# UART-Interface.net
KiCad netlist of a schematic drawn in Altium Designer
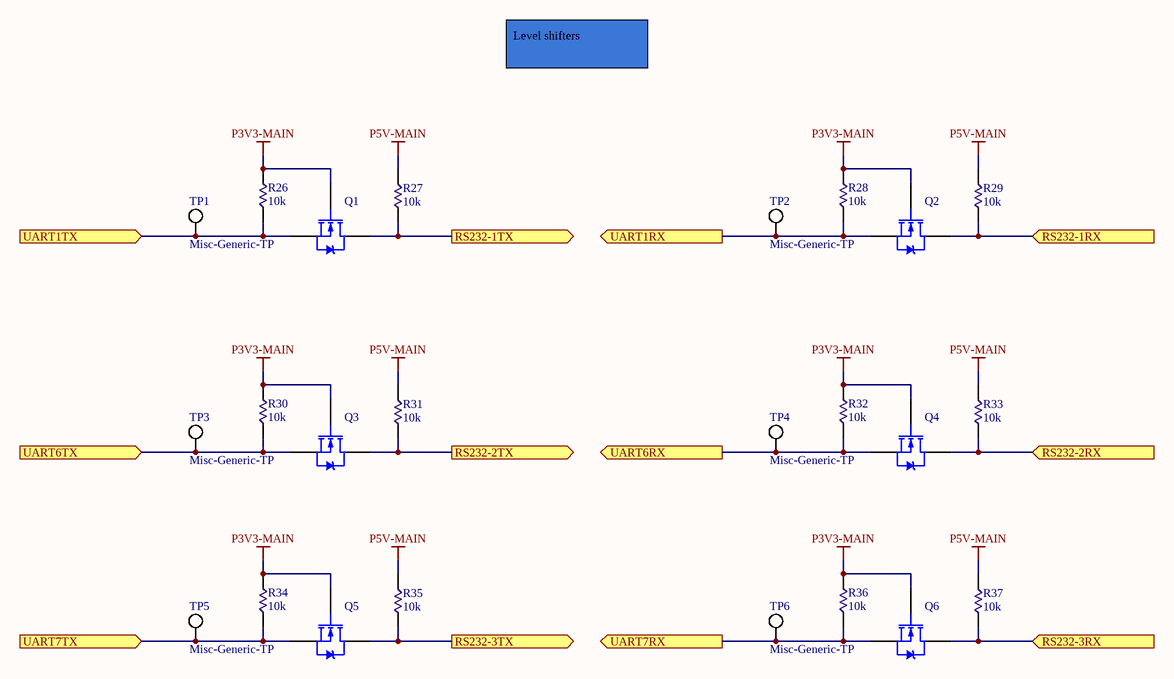
[diagram p0: UART-Interface.SchDoc]

(export (version "E")
  (design (tool "Eeschema 10.0.6"))
  (components
    (comp (ref "Q1")
      (value "BSS138Q-7-F")
      (footprint "FOOTPRINT-DINC-SOT23-1G2S3D")
      (description "N-Channel Logic Level Enhancement Mode Field Effect Transistor")
      (fields (field (name "PUBLISHER") "Altium Limited"))
      (libsource (lib "HR-Master-Integrated") (part "Transistor-DiodesInc-BSS138-1G2S3D"))
    )
    (comp (ref "Q2")
      (value "BSS138Q-7-F")
      (footprint "FOOTPRINT-DINC-SOT23-1G2S3D")
      (description "N-Channel Logic Level Enhancement Mode Field Effect Transistor")
      (fields (field (name "PUBLISHER") "Altium Limited"))
      (libsource (lib "HR-Master-Integrated") (part "Transistor-DiodesInc-BSS138-1G2S3D"))
    )
    (comp (ref "Q3")
      (value "BSS138Q-7-F")
      (footprint "FOOTPRINT-DINC-SOT23-1G2S3D")
      (description "N-Channel Logic Level Enhancement Mode Field Effect Transistor")
      (fields (field (name "PUBLISHER") "Altium Limited"))
      (libsource (lib "HR-Master-Integrated") (part "Transistor-DiodesInc-BSS138-1G2S3D"))
    )
    (comp (ref "Q4")
      (value "BSS138Q-7-F")
      (footprint "FOOTPRINT-DINC-SOT23-1G2S3D")
      (description "N-Channel Logic Level Enhancement Mode Field Effect Transistor")
      (fields (field (name "PUBLISHER") "Altium Limited"))
      (libsource (lib "HR-Master-Integrated") (part "Transistor-DiodesInc-BSS138-1G2S3D"))
    )
    (comp (ref "Q5")
      (value "BSS138Q-7-F")
      (footprint "FOOTPRINT-DINC-SOT23-1G2S3D")
      (description "N-Channel Logic Level Enhancement Mode Field Effect Transistor")
      (fields (field (name "PUBLISHER") "Altium Limited"))
      (libsource (lib "HR-Master-Integrated") (part "Transistor-DiodesInc-BSS138-1G2S3D"))
    )
    (comp (ref "Q6")
      (value "BSS138Q-7-F")
      (footprint "FOOTPRINT-DINC-SOT23-1G2S3D")
      (description "N-Channel Logic Level Enhancement Mode Field Effect Transistor")
      (fields (field (name "PUBLISHER") "Altium Limited"))
      (libsource (lib "HR-Master-Integrated") (part "Transistor-DiodesInc-BSS138-1G2S3D"))
    )
    (comp (ref "R26")
      (value "10k")
      (footprint "FOOTPRINT-0805-GEN")
      (description "1/8 Watt Surface Mount Resistor")
      (fields (field (name "Comment") "SMC"))
      (libsource (lib "HR-Master-Integrated") (part "Resistor-Generic-0805-2012"))
    )
    (comp (ref "R27")
      (value "10k")
      (footprint "FOOTPRINT-0805-GEN")
      (description "1/8 Watt Surface Mount Resistor")
      (fields (field (name "Comment") "SMC"))
      (libsource (lib "HR-Master-Integrated") (part "Resistor-Generic-0805-2012"))
    )
    (comp (ref "R28")
      (value "10k")
      (footprint "FOOTPRINT-0805-GEN")
      (description "1/8 Watt Surface Mount Resistor")
      (fields (field (name "Comment") "SMC"))
      (libsource (lib "HR-Master-Integrated") (part "Resistor-Generic-0805-2012"))
    )
    (comp (ref "R29")
      (value "10k")
      (footprint "FOOTPRINT-0805-GEN")
      (description "1/8 Watt Surface Mount Resistor")
      (fields (field (name "Comment") "SMC"))
      (libsource (lib "HR-Master-Integrated") (part "Resistor-Generic-0805-2012"))
    )
    (comp (ref "R30")
      (value "10k")
      (footprint "FOOTPRINT-0805-GEN")
      (description "1/8 Watt Surface Mount Resistor")
      (fields (field (name "Comment") "SMC"))
      (libsource (lib "HR-Master-Integrated") (part "Resistor-Generic-0805-2012"))
    )
    (comp (ref "R31")
      (value "10k")
      (footprint "FOOTPRINT-0805-GEN")
      (description "1/8 Watt Surface Mount Resistor")
      (fields (field (name "Comment") "SMC"))
      (libsource (lib "HR-Master-Integrated") (part "Resistor-Generic-0805-2012"))
    )
    (comp (ref "R32")
      (value "10k")
      (footprint "FOOTPRINT-0805-GEN")
      (description "1/8 Watt Surface Mount Resistor")
      (fields (field (name "Comment") "SMC"))
      (libsource (lib "HR-Master-Integrated") (part "Resistor-Generic-0805-2012"))
    )
    (comp (ref "R33")
      (value "10k")
      (footprint "FOOTPRINT-0805-GEN")
      (description "1/8 Watt Surface Mount Resistor")
      (fields (field (name "Comment") "SMC"))
      (libsource (lib "HR-Master-Integrated") (part "Resistor-Generic-0805-2012"))
    )
    (comp (ref "R34")
      (value "10k")
      (footprint "FOOTPRINT-0805-GEN")
      (description "1/8 Watt Surface Mount Resistor")
      (fields (field (name "Comment") "SMC"))
      (libsource (lib "HR-Master-Integrated") (part "Resistor-Generic-0805-2012"))
    )
    (comp (ref "R35")
      (value "10k")
      (footprint "FOOTPRINT-0805-GEN")
      (description "1/8 Watt Surface Mount Resistor")
      (fields (field (name "Comment") "SMC"))
      (libsource (lib "HR-Master-Integrated") (part "Resistor-Generic-0805-2012"))
    )
    (comp (ref "R36")
      (value "10k")
      (footprint "FOOTPRINT-0805-GEN")
      (description "1/8 Watt Surface Mount Resistor")
      (fields (field (name "Comment") "SMC"))
      (libsource (lib "HR-Master-Integrated") (part "Resistor-Generic-0805-2012"))
    )
    (comp (ref "R37")
      (value "10k")
      (footprint "FOOTPRINT-0805-GEN")
      (description "1/8 Watt Surface Mount Resistor")
      (fields (field (name "Comment") "SMC"))
      (libsource (lib "HR-Master-Integrated") (part "Resistor-Generic-0805-2012"))
    )
    (comp (ref "TP1")
      (value "Misc-Generic-TP")
      (footprint "FOOTPRINT-GENERIC-TP-VIA-1MM")
      (libsource (lib "Generic") (part "Misc-Generic-TP"))
    )
    (comp (ref "TP2")
      (value "Misc-Generic-TP")
      (footprint "FOOTPRINT-GENERIC-TP-VIA-1MM")
      (libsource (lib "Generic") (part "Misc-Generic-TP"))
    )
    (comp (ref "TP3")
      (value "Misc-Generic-TP")
      (footprint "FOOTPRINT-GENERIC-TP-VIA-1MM")
      (libsource (lib "Generic") (part "Misc-Generic-TP"))
    )
    (comp (ref "TP4")
      (value "Misc-Generic-TP")
      (footprint "FOOTPRINT-GENERIC-TP-VIA-1MM")
      (libsource (lib "Generic") (part "Misc-Generic-TP"))
    )
    (comp (ref "TP5")
      (value "Misc-Generic-TP")
      (footprint "FOOTPRINT-GENERIC-TP-VIA-1MM")
      (libsource (lib "Generic") (part "Misc-Generic-TP"))
    )
    (comp (ref "TP6")
      (value "Misc-Generic-TP")
      (footprint "FOOTPRINT-GENERIC-TP-VIA-1MM")
      (libsource (lib "Generic") (part "Misc-Generic-TP"))
    )
  )
  (nets
    (net (code "1") (name "/RS232-1RX") (class "Default")
      (node (ref "Q2") (pin "3") (pinfunction "D_3") (pintype "passive"))
      (node (ref "R29") (pin "2") (pinfunction "2_2") (pintype "passive"))
    )
    (net (code "2") (name "/RS232-1TX") (class "Default")
      (node (ref "Q1") (pin "3") (pinfunction "D_3") (pintype "passive"))
      (node (ref "R27") (pin "2") (pinfunction "2_2") (pintype "passive"))
    )
    (net (code "3") (name "/RS232-2RX") (class "Default")
      (node (ref "Q4") (pin "3") (pinfunction "D_3") (pintype "passive"))
      (node (ref "R33") (pin "2") (pinfunction "2_2") (pintype "passive"))
    )
    (net (code "4") (name "/RS232-2TX") (class "Default")
      (node (ref "Q3") (pin "3") (pinfunction "D_3") (pintype "passive"))
      (node (ref "R31") (pin "2") (pinfunction "2_2") (pintype "passive"))
    )
    (net (code "5") (name "/RS232-3RX") (class "Default")
      (node (ref "Q6") (pin "3") (pinfunction "D_3") (pintype "passive"))
      (node (ref "R37") (pin "2") (pinfunction "2_2") (pintype "passive"))
    )
    (net (code "6") (name "/RS232-3TX") (class "Default")
      (node (ref "Q5") (pin "3") (pinfunction "D_3") (pintype "passive"))
      (node (ref "R35") (pin "2") (pinfunction "2_2") (pintype "passive"))
    )
    (net (code "7") (name "/UART1RX") (class "Default")
      (node (ref "Q2") (pin "2") (pinfunction "S_2") (pintype "passive"))
      (node (ref "R28") (pin "1") (pinfunction "1_1") (pintype "passive"))
      (node (ref "TP2") (pin "1") (pinfunction "TP_1") (pintype "passive"))
    )
    (net (code "8") (name "/UART1TX") (class "Default")
      (node (ref "Q1") (pin "2") (pinfunction "S_2") (pintype "passive"))
      (node (ref "R26") (pin "1") (pinfunction "1_1") (pintype "passive"))
      (node (ref "TP1") (pin "1") (pinfunction "TP_1") (pintype "passive"))
    )
    (net (code "9") (name "/UART6RX") (class "Default")
      (node (ref "Q4") (pin "2") (pinfunction "S_2") (pintype "passive"))
      (node (ref "R32") (pin "1") (pinfunction "1_1") (pintype "passive"))
      (node (ref "TP4") (pin "1") (pinfunction "TP_1") (pintype "passive"))
    )
    (net (code "10") (name "/UART6TX") (class "Default")
      (node (ref "Q3") (pin "2") (pinfunction "S_2") (pintype "passive"))
      (node (ref "R30") (pin "1") (pinfunction "1_1") (pintype "passive"))
      (node (ref "TP3") (pin "1") (pinfunction "TP_1") (pintype "passive"))
    )
    (net (code "11") (name "/UART7RX") (class "Default")
      (node (ref "Q6") (pin "2") (pinfunction "S_2") (pintype "passive"))
      (node (ref "R36") (pin "1") (pinfunction "1_1") (pintype "passive"))
      (node (ref "TP6") (pin "1") (pinfunction "TP_1") (pintype "passive"))
    )
    (net (code "12") (name "/UART7TX") (class "Default")
      (node (ref "Q5") (pin "2") (pinfunction "S_2") (pintype "passive"))
      (node (ref "R34") (pin "1") (pinfunction "1_1") (pintype "passive"))
      (node (ref "TP5") (pin "1") (pinfunction "TP_1") (pintype "passive"))
    )
    (net (code "13") (name "P3V3-MAIN") (class "Default")
      (node (ref "Q1") (pin "1") (pinfunction "G_1") (pintype "passive"))
      (node (ref "Q2") (pin "1") (pinfunction "G_1") (pintype "passive"))
      (node (ref "Q3") (pin "1") (pinfunction "G_1") (pintype "passive"))
      (node (ref "Q4") (pin "1") (pinfunction "G_1") (pintype "passive"))
      (node (ref "Q5") (pin "1") (pinfunction "G_1") (pintype "passive"))
      (node (ref "Q6") (pin "1") (pinfunction "G_1") (pintype "passive"))
      (node (ref "R26") (pin "2") (pinfunction "2_2") (pintype "passive"))
      (node (ref "R28") (pin "2") (pinfunction "2_2") (pintype "passive"))
      (node (ref "R30") (pin "2") (pinfunction "2_2") (pintype "passive"))
      (node (ref "R32") (pin "2") (pinfunction "2_2") (pintype "passive"))
      (node (ref "R34") (pin "2") (pinfunction "2_2") (pintype "passive"))
      (node (ref "R36") (pin "2") (pinfunction "2_2") (pintype "passive"))
    )
    (net (code "14") (name "P5V-MAIN") (class "Default")
      (node (ref "R27") (pin "1") (pinfunction "1_1") (pintype "passive"))
      (node (ref "R29") (pin "1") (pinfunction "1_1") (pintype "passive"))
      (node (ref "R31") (pin "1") (pinfunction "1_1") (pintype "passive"))
      (node (ref "R33") (pin "1") (pinfunction "1_1") (pintype "passive"))
      (node (ref "R35") (pin "1") (pinfunction "1_1") (pintype "passive"))
      (node (ref "R37") (pin "1") (pinfunction "1_1") (pintype "passive"))
    )
  )
)
